# CH340.net
KiCad netlist of a schematic drawn in Altium Designer
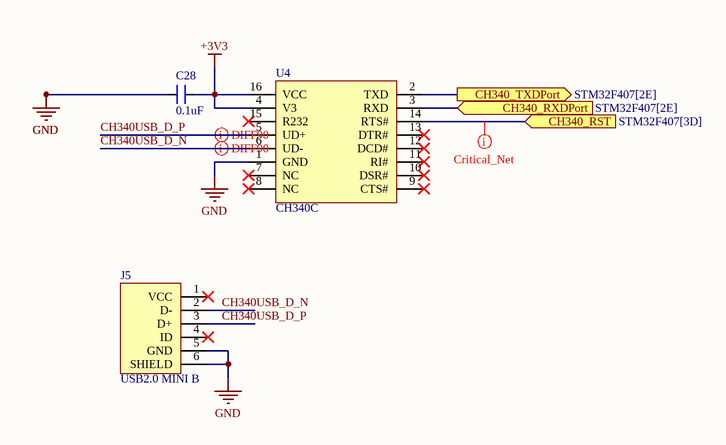
[diagram p0: CH340.SchDoc]

(export (version "E")
  (design (tool "Eeschema 10.0.6"))
  (components
    (comp (ref "C28")
      (value "0.1uF")
      (footprint "CAP_0805")
      (description "0.1µF ±10% 50V Ceramic Capacitor X7R 0805 (2012 Metric)")
      (fields
        (field (name "MANUFACTURER") "Samsung")
        (field (name "MANUFACTURER PART NUMBER") "CL21B104KBCNNNC")
      )
      (libsource (lib "ESTEEMPCBLIB") (part "CAP_0.1uF-50V-10%-0805"))
    )
    (comp (ref "J5")
      (value "USB2.0 MINI B")
      (footprint "CON_690-005-299-043")
      (description "USB - mini B USB 2.0 Receptacle Connector 5 Position Surface Mount, Right Angle")
      (fields
        (field (name "MANUFACTURER") "EDAC")
        (field (name "MANUFACTURER PART NUMBER") "690-005-299-043")
      )
      (libsource (lib "ESTEEMPCBLIB") (part "CON_USB2.0-MINIB-SMD"))
    )
    (comp (ref "U4")
      (value "CH340C")
      (footprint "SOIC16_50_284_25X90_SMT")
      (description "USB Bridge, USB to UART USB 2.0 UART Interface")
      (fields (field (name "MANUFACTURER") "Olimex"))
      (libsource (lib "ESTEEMPCBLIB") (part "IC_CH340C"))
    )
  )
  (nets
    (net (code "1") (name "+3V3") (class "Default")
      (node (ref "C28") (pin "1") (pinfunction "1_1") (pintype "passive"))
      (node (ref "U4") (pin "16") (pinfunction "VCC_16") (pintype "passive"))
      (node (ref "U4") (pin "4") (pinfunction "V3_4") (pintype "passive"))
    )
    (net (code "2") (name "/CH340USB_D_N") (class "Default")
      (node (ref "J5") (pin "2") (pinfunction "D-_2") (pintype "passive"))
      (node (ref "U4") (pin "6") (pinfunction "UD-_6") (pintype "passive"))
    )
    (net (code "3") (name "/CH340USB_D_P") (class "Default")
      (node (ref "J5") (pin "3") (pinfunction "D+_3") (pintype "passive"))
      (node (ref "U4") (pin "5") (pinfunction "UD+_5") (pintype "passive"))
    )
    (net (code "4") (name "/CH340_RST") (class "Default")
      (node (ref "U4") (pin "14") (pinfunction "RTS#_14") (pintype "passive"))
    )
    (net (code "5") (name "/CH340_RXDPort") (class "Default")
      (node (ref "U4") (pin "3") (pinfunction "RXD_3") (pintype "passive"))
    )
    (net (code "6") (name "/CH340_TXDPort") (class "Default")
      (node (ref "U4") (pin "2") (pinfunction "TXD_2") (pintype "passive"))
    )
    (net (code "7") (name "GND") (class "Default")
      (node (ref "C28") (pin "2") (pinfunction "2_2") (pintype "passive"))
      (node (ref "J5") (pin "5") (pinfunction "GND_5") (pintype "passive"))
      (node (ref "J5") (pin "6") (pinfunction "SHIELD_6") (pintype "passive"))
      (node (ref "U4") (pin "1") (pinfunction "GND_1") (pintype "passive"))
    )
    (net (code "8") (name "unconnected-(J5-ID-Pad4)") (class "Default")
      (node (ref "J5") (pin "4") (pinfunction "ID_4") (pintype "passive+no_connect"))
    )
    (net (code "9") (name "unconnected-(J5-VCC-Pad1)") (class "Default")
      (node (ref "J5") (pin "1") (pinfunction "VCC_1") (pintype "passive+no_connect"))
    )
    (net (code "10") (name "unconnected-(U4-CTS#-Pad9)") (class "Default")
      (node (ref "U4") (pin "9") (pinfunction "CTS#_9") (pintype "passive+no_connect"))
    )
    (net (code "11") (name "unconnected-(U4-DCD#-Pad12)") (class "Default")
      (node (ref "U4") (pin "12") (pinfunction "DCD#_12") (pintype "passive+no_connect"))
    )
    (net (code "12") (name "unconnected-(U4-DSR#-Pad10)") (class "Default")
      (node (ref "U4") (pin "10") (pinfunction "DSR#_10") (pintype "passive+no_connect"))
    )
    (net (code "13") (name "unconnected-(U4-DTR#-Pad13)") (class "Default")
      (node (ref "U4") (pin "13") (pinfunction "DTR#_13") (pintype "passive+no_connect"))
    )
    (net (code "14") (name "unconnected-(U4-NC-Pad7)") (class "Default")
      (node (ref "U4") (pin "7") (pinfunction "NC_7") (pintype "passive+no_connect"))
    )
    (net (code "15") (name "unconnected-(U4-NC-Pad8)") (class "Default")
      (node (ref "U4") (pin "8") (pinfunction "NC_8") (pintype "passive+no_connect"))
    )
    (net (code "16") (name "unconnected-(U4-R232-Pad15)") (class "Default")
      (node (ref "U4") (pin "15") (pinfunction "R232_15") (pintype "passive+no_connect"))
    )
    (net (code "17") (name "unconnected-(U4-RI#-Pad11)") (class "Default")
      (node (ref "U4") (pin "11") (pinfunction "RI#_11") (pintype "passive+no_connect"))
    )
  )
)
